# pc.net
KiCad netlist of a schematic drawn in EAGLE
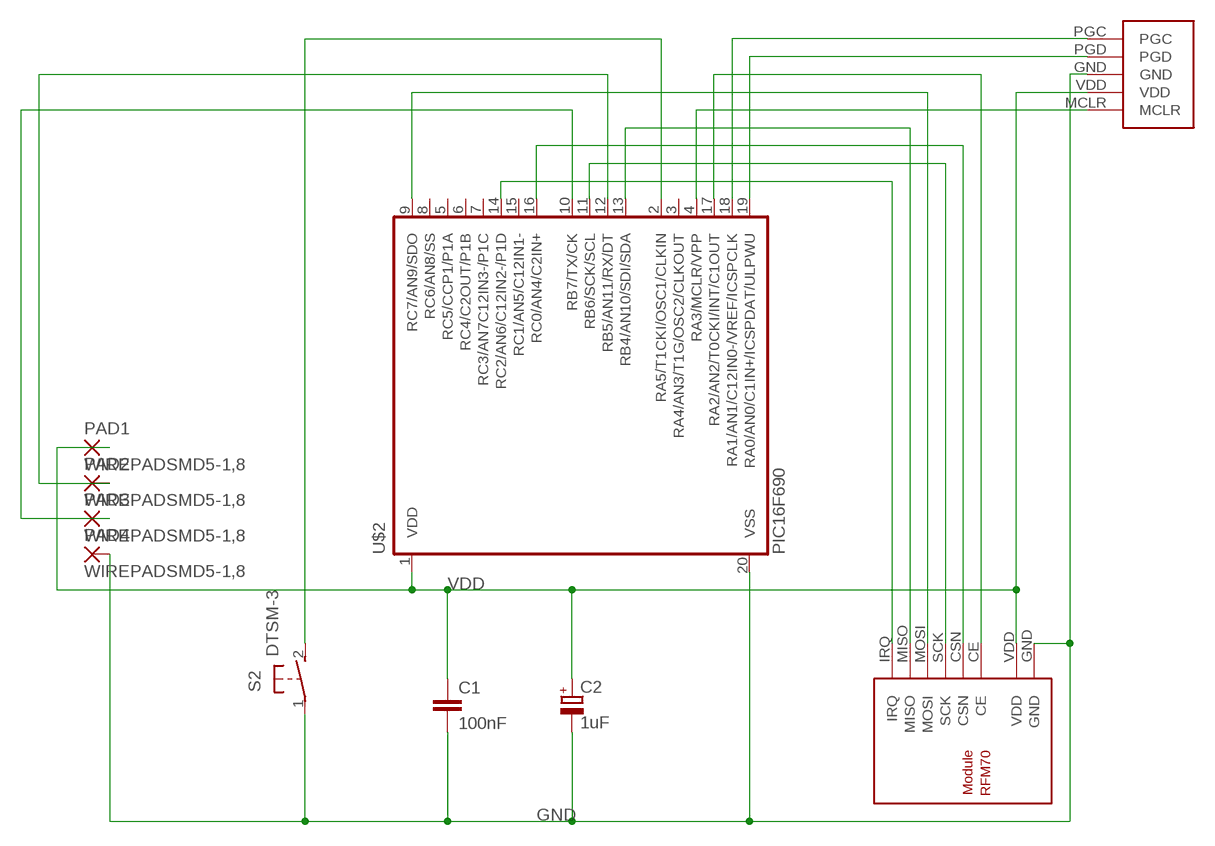
[diagram p0: schematic, sheet 1]

(export (version "E")
  (design (tool "Eeschema 10.0.6"))
  (components
    (comp (ref "C1")
      (value "100nF")
      (footprint "eagle-import:C2012")
      (libsource (lib "eagle-import") (part "C-EUC2012"))
    )
    (comp (ref "C2")
      (value "1uF")
      (footprint "eagle-import:SMC_A")
      (libsource (lib "eagle-import") (part "CPOL-EUSMCA"))
    )
    (comp (ref "PAD1")
      (value "WIREPADSMD5-1,8")
      (footprint "eagle-import:5-1,8")
      (libsource (lib "eagle-import") (part "WIREPADSMD5-1,8"))
    )
    (comp (ref "PAD2")
      (value "WIREPADSMD5-1,8")
      (footprint "eagle-import:5-1,8")
      (libsource (lib "eagle-import") (part "WIREPADSMD5-1,8"))
    )
    (comp (ref "PAD3")
      (value "WIREPADSMD5-1,8")
      (footprint "eagle-import:5-1,8")
      (libsource (lib "eagle-import") (part "WIREPADSMD5-1,8"))
    )
    (comp (ref "PAD4")
      (value "WIREPADSMD5-1,8")
      (footprint "eagle-import:5-1,8")
      (libsource (lib "eagle-import") (part "WIREPADSMD5-1,8"))
    )
    (comp (ref "S2")
      (value "DTSM-3")
      (footprint "eagle-import:DTSM-3")
      (libsource (lib "eagle-import") (part "DTSM-3"))
    )
    (comp (ref "U$1")
      (value "RFM70")
      (footprint "eagle-import:RFM70")
      (libsource (lib "eagle-import") (part "RFM70"))
    )
    (comp (ref "U$2")
      (value "PIC16F690")
      (footprint "eagle-import:SSOP20")
      (libsource (lib "eagle-import") (part "PIC16F690"))
    )
    (comp (ref "U$3")
      (value "PROGRAMMINGHEADERDIP")
      (footprint "eagle-import:PROGHEADER")
      (libsource (lib "eagle-import") (part "PROGRAMMINGHEADERDIP"))
    )
  )
  (nets
    (net (code "1") (name "/GND") (class "Default")
      (node (ref "C1") (pin "2") (pinfunction "2_2") (pintype "passive"))
      (node (ref "C2") (pin "-") (pinfunction "-_-") (pintype "passive"))
      (node (ref "PAD4") (pin "1") (pinfunction "P_1") (pintype "passive"))
      (node (ref "S2") (pin "1") (pinfunction "1_1") (pintype "passive"))
      (node (ref "U$1") (pin "GND") (pinfunction "GND_GND") (pintype "power_in"))
      (node (ref "U$2") (pin "20") (pinfunction "VSS_20") (pintype "power_in"))
      (node (ref "U$3") (pin "GND") (pinfunction "GND_GND") (pintype "power_in"))
    )
    (net (code "2") (name "/VDD") (class "Default")
      (node (ref "C1") (pin "1") (pinfunction "1_1") (pintype "passive"))
      (node (ref "C2") (pin "+") (pinfunction "+_+") (pintype "passive"))
      (node (ref "PAD1") (pin "1") (pinfunction "P_1") (pintype "passive"))
      (node (ref "U$1") (pin "VDD") (pinfunction "VDD_VDD") (pintype "power_in"))
      (node (ref "U$2") (pin "1") (pinfunction "VDD_1") (pintype "power_in"))
      (node (ref "U$3") (pin "VDD") (pinfunction "VDD_VDD") (pintype "power_in"))
    )
    (net (code "3") (name "Net-(PAD2-P)") (class "Default")
      (node (ref "PAD2") (pin "1") (pinfunction "P_1") (pintype "passive"))
      (node (ref "U$2") (pin "12") (pinfunction "RB5/AN11/RX/DT_12") (pintype "bidirectional"))
    )
    (net (code "4") (name "Net-(PAD3-P)") (class "Default")
      (node (ref "PAD3") (pin "1") (pinfunction "P_1") (pintype "passive"))
      (node (ref "U$2") (pin "10") (pinfunction "RB7/TX/CK_10") (pintype "bidirectional"))
    )
    (net (code "5") (name "Net-(U$2-RA0{slash}AN0{slash}C1IN+{slash}ICSPDAT{slash}ULPWU)") (class "Default")
      (node (ref "U$2") (pin "19") (pinfunction "RA0/AN0/C1IN+/ICSPDAT/ULPWU_19") (pintype "bidirectional"))
      (node (ref "U$3") (pin "PGD") (pinfunction "PGD_PGD") (pintype "bidirectional"))
    )
    (net (code "6") (name "Net-(U$2-RA1{slash}AN1{slash}C12IN0-{slash}VREF{slash}ICSPCLK)") (class "Default")
      (node (ref "U$2") (pin "18") (pinfunction "RA1/AN1/C12IN0-/VREF/ICSPCLK_18") (pintype "bidirectional"))
      (node (ref "U$3") (pin "PGC") (pinfunction "PGC_PGC") (pintype "bidirectional"))
    )
    (net (code "7") (name "Net-(U$2-RA2{slash}AN2{slash}T0CKI{slash}INT{slash}C1OUT)") (class "Default")
      (node (ref "U$1") (pin "CE") (pinfunction "CE_CE") (pintype "bidirectional"))
      (node (ref "U$2") (pin "17") (pinfunction "RA2/AN2/T0CKI/INT/C1OUT_17") (pintype "bidirectional"))
    )
    (net (code "8") (name "Net-(U$2-RA3{slash}MCLR{slash}VPP)") (class "Default")
      (node (ref "U$2") (pin "4") (pinfunction "RA3/MCLR/VPP_4") (pintype "bidirectional"))
      (node (ref "U$3") (pin "MCLR") (pinfunction "MCLR_MCLR") (pintype "output"))
    )
    (net (code "9") (name "Net-(U$2-RA5{slash}T1CKI{slash}OSC1{slash}CLKIN)") (class "Default")
      (node (ref "S2") (pin "2") (pinfunction "2_2") (pintype "passive"))
      (node (ref "U$2") (pin "2") (pinfunction "RA5/T1CKI/OSC1/CLKIN_2") (pintype "bidirectional"))
    )
    (net (code "10") (name "Net-(U$2-RB4{slash}AN10{slash}SDI{slash}SDA)") (class "Default")
      (node (ref "U$1") (pin "MISO") (pinfunction "MISO_MISO") (pintype "bidirectional"))
      (node (ref "U$2") (pin "13") (pinfunction "RB4/AN10/SDI/SDA_13") (pintype "bidirectional"))
    )
    (net (code "11") (name "Net-(U$2-RB6{slash}SCK{slash}SCL)") (class "Default")
      (node (ref "U$1") (pin "SCK") (pinfunction "SCK_SCK") (pintype "bidirectional"))
      (node (ref "U$2") (pin "11") (pinfunction "RB6/SCK/SCL_11") (pintype "bidirectional"))
    )
    (net (code "12") (name "Net-(U$2-RC0{slash}AN4{slash}C2IN+)") (class "Default")
      (node (ref "U$1") (pin "CSN") (pinfunction "CSN_CSN") (pintype "bidirectional"))
      (node (ref "U$2") (pin "16") (pinfunction "RC0/AN4/C2IN+_16") (pintype "bidirectional"))
    )
    (net (code "13") (name "Net-(U$2-RC2{slash}AN6{slash}C12IN2-{slash}P1D)") (class "Default")
      (node (ref "U$1") (pin "IRQ") (pinfunction "IRQ_IRQ") (pintype "bidirectional"))
      (node (ref "U$2") (pin "14") (pinfunction "RC2/AN6/C12IN2-/P1D_14") (pintype "bidirectional"))
    )
    (net (code "14") (name "Net-(U$2-RC7{slash}AN9{slash}SDO)") (class "Default")
      (node (ref "U$1") (pin "MOSI") (pinfunction "MOSI_MOSI") (pintype "bidirectional"))
      (node (ref "U$2") (pin "9") (pinfunction "RC7/AN9/SDO_9") (pintype "bidirectional"))
    )
    (net (code "15") (name "unconnected-(U$2-RA4{slash}AN3{slash}T1G{slash}OSC2{slash}CLKOUT-Pad3)") (class "Default")
      (node (ref "U$2") (pin "3") (pinfunction "RA4/AN3/T1G/OSC2/CLKOUT_3") (pintype "bidirectional"))
    )
    (net (code "16") (name "unconnected-(U$2-RC1{slash}AN5{slash}C12IN1--Pad15)") (class "Default")
      (node (ref "U$2") (pin "15") (pinfunction "RC1/AN5/C12IN1-_15") (pintype "bidirectional"))
    )
    (net (code "17") (name "unconnected-(U$2-RC3{slash}AN7C12IN3-{slash}P1C-Pad7)") (class "Default")
      (node (ref "U$2") (pin "7") (pinfunction "RC3/AN7C12IN3-/P1C_7") (pintype "bidirectional"))
    )
    (net (code "18") (name "unconnected-(U$2-RC4{slash}C2OUT{slash}P1B-Pad6)") (class "Default")
      (node (ref "U$2") (pin "6") (pinfunction "RC4/C2OUT/P1B_6") (pintype "bidirectional"))
    )
    (net (code "19") (name "unconnected-(U$2-RC5{slash}CCP1{slash}P1A-Pad5)") (class "Default")
      (node (ref "U$2") (pin "5") (pinfunction "RC5/CCP1/P1A_5") (pintype "bidirectional"))
    )
    (net (code "20") (name "unconnected-(U$2-RC6{slash}AN8{slash}SS-Pad8)") (class "Default")
      (node (ref "U$2") (pin "8") (pinfunction "RC6/AN8/SS_8") (pintype "bidirectional"))
    )
  )
)
